# w-dmx-schematic.net
KiCad netlist of a schematic drawn in EasyEDA Pro
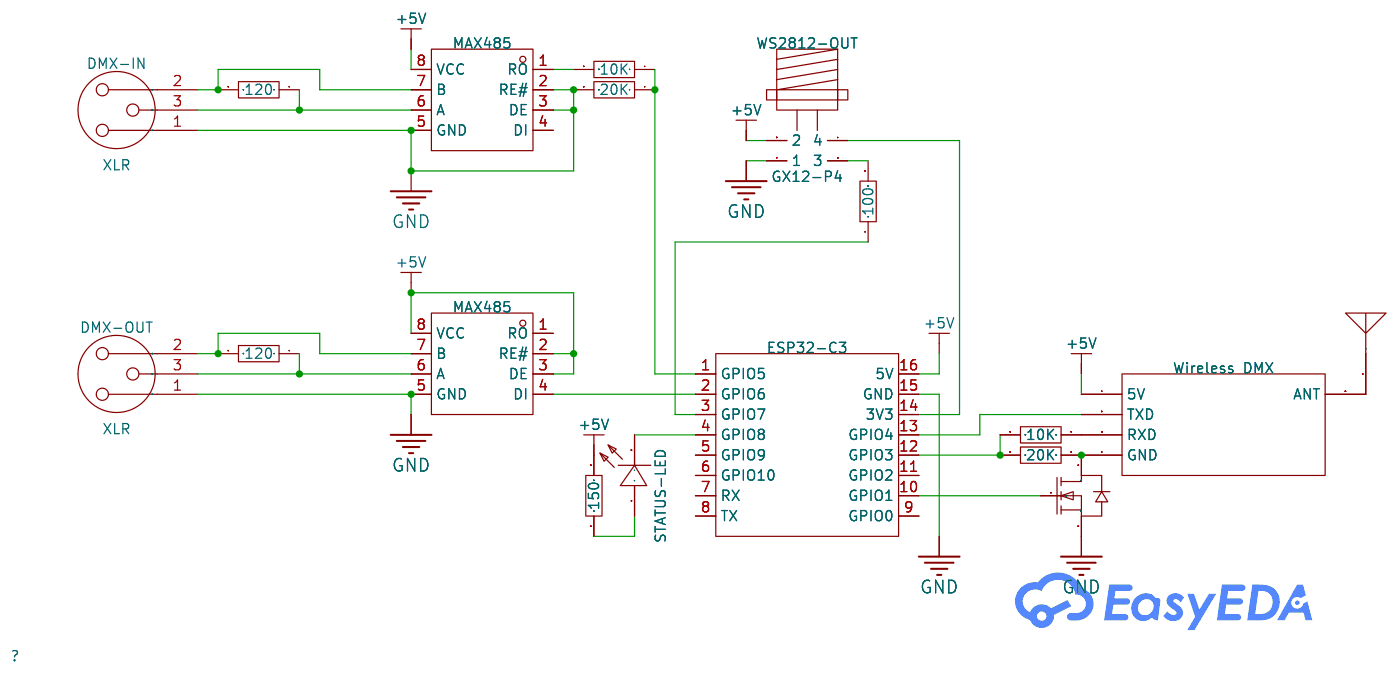
[diagram p0: schematic sheet]

(export (version "E")
  (design (tool "Eeschema 10.0.6"))
  (components
    (comp (ref "DMX-IN")
      (value "XLR")
      (footprint "easyedapro:CONN-TH_XLR-328")
      (description "Number of Pins:3P Gender:Female Mounting Type:Right Angle Current Rating:3A Voltage Rating:50V")
      (fields (field (name "Manufacturer") "HOOYA(皓宇电子)"))
      (libsource (lib "easyedapro") (part "XLR-328"))
    )
    (comp (ref "DMX-OUT")
      (value "XLR")
      (footprint "easyedapro:CONN-TH_XLR-328")
      (description "Number of Pins:3P Gender:Female Mounting Type:Right Angle Current Rating:3A Voltage Rating:50V")
      (fields (field (name "Manufacturer") "HOOYA(皓宇电子)"))
      (libsource (lib "easyedapro") (part "XLR-328"))
    )
    (comp (ref "Q1")
      (value "IRF530")
      (footprint "easyedapro:TO-220AB-3_L10.4-W4.6-P2.54-L")
      (fields (field (name "Manufacturer") "TI(德州仪器)"))
      (libsource (lib "easyedapro") (part "IRF530"))
    )
    (comp (ref "R2") (value "10K") (footprint "easyedapro:R0603") (libsource (lib "easyedapro") (part "Res")))
    (comp (ref "R3") (value "20K") (footprint "easyedapro:R0603") (libsource (lib "easyedapro") (part "Res")))
    (comp (ref "R4") (value "120") (footprint "easyedapro:R0603") (libsource (lib "easyedapro") (part "Res")))
    (comp (ref "R5") (value "120") (footprint "easyedapro:R0603") (libsource (lib "easyedapro") (part "Res")))
    (comp (ref "R6") (value "100") (footprint "easyedapro:R0603") (libsource (lib "easyedapro") (part "Res")))
    (comp (ref "R7") (value "150") (footprint "easyedapro:R0603") (libsource (lib "easyedapro") (part "Res")))
    (comp (ref "R8") (value "10K") (footprint "easyedapro:R0603") (libsource (lib "easyedapro") (part "Res")))
    (comp (ref "R9") (value "20K") (footprint "easyedapro:R0603") (libsource (lib "easyedapro") (part "Res")))
    (comp (ref "STATUS-LED")
      (value "KT-0805Y")
      (footprint "easyedapro:LED0805-R-RD")
      (fields (field (name "Manufacturer") "KENTO"))
      (libsource (lib "easyedapro") (part "17-21SUYC/TR8"))
    )
    (comp (ref "U2")
      (value "MAX485")
      (footprint "easyedapro:SOP-8_L4.9-W3.9-P1.27-LS6.0-BL")
      (fields (field (name "Manufacturer") "ElecSuper(静芯微)"))
      (libsource (lib "easyedapro") (part "MAX485EESA+T(ES)"))
    )
    (comp (ref "U3")
      (value "MAX485")
      (footprint "easyedapro:SOP-8_L4.9-W3.9-P1.27-LS6.0-BL")
      (fields (field (name "Manufacturer") "ElecSuper(静芯微)"))
      (libsource (lib "easyedapro") (part "MAX485EESA+T(ES)"))
    )
    (comp (ref "U4") (value "Wireless DMX") (libsource (lib "easyedapro") (part "Wireless DMX")))
    (comp (ref "U5") (value "~") (libsource (lib "easyedapro") (part "antenna")))
    (comp (ref "U6")
      (value "ESP32-C3")
      (footprint "easyedapro:COMM-SMD_16P-L22.5-W18.0-P2.54-TL")
      (libsource (lib "easyedapro") (part "ESP32C3-SuperMini"))
    )
    (comp (ref "WS2812-OUT")
      (value "GX12-P4")
      (footprint "easyedapro:CONN-TH_GX12C-4P")
      (libsource (lib "easyedapro") (part "WBC0202-150A"))
    )
  )
  (nets
    (net (code "1") (name "+5V") (class "Default")
      (node (ref "R7") (pin "2") (pinfunction "2_2") (pintype "input"))
      (node (ref "U2") (pin "8") (pinfunction "VCC_8") (pintype "unspecified"))
      (node (ref "U3") (pin "2") (pinfunction "RE#_2") (pintype "unspecified"))
      (node (ref "U3") (pin "3") (pinfunction "DE_3") (pintype "unspecified"))
      (node (ref "U3") (pin "8") (pinfunction "VCC_8") (pintype "unspecified"))
      (node (ref "U4") (pin "4") (pinfunction "5V_4") (pintype "input"))
      (node (ref "U6") (pin "16") (pinfunction "5V_16") (pintype "unspecified"))
      (node (ref "WS2812-OUT") (pin "2") (pinfunction "2_2") (pintype "unspecified"))
    )
    (net (code "2") (name "GND") (class "Default")
      (node (ref "DMX-IN") (pin "1") (pinfunction "1_1") (pintype "unspecified"))
      (node (ref "DMX-OUT") (pin "1") (pinfunction "1_1") (pintype "unspecified"))
      (node (ref "Q1") (pin "3") (pinfunction "S_3") (pintype "unspecified"))
      (node (ref "R3") (pin "2") (pinfunction "2_2") (pintype "input"))
      (node (ref "U2") (pin "2") (pinfunction "RE#_2") (pintype "unspecified"))
      (node (ref "U2") (pin "3") (pinfunction "DE_3") (pintype "unspecified"))
      (node (ref "U2") (pin "5") (pinfunction "GND_5") (pintype "unspecified"))
      (node (ref "U3") (pin "5") (pinfunction "GND_5") (pintype "unspecified"))
      (node (ref "U6") (pin "15") (pinfunction "GND_15") (pintype "unspecified"))
      (node (ref "WS2812-OUT") (pin "1") (pinfunction "1_1") (pintype "unspecified"))
    )
    (net (code "3") (name "Net-(Q1-D)") (class "Default")
      (node (ref "Q1") (pin "2") (pinfunction "D_2") (pintype "unspecified"))
      (node (ref "R9") (pin "1") (pinfunction "1_1") (pintype "input"))
      (node (ref "U4") (pin "1") (pinfunction "GND_1") (pintype "input"))
    )
    (net (code "4") (name "Net-(Q1-G)") (class "Default")
      (node (ref "Q1") (pin "1") (pinfunction "G_1") (pintype "unspecified"))
      (node (ref "U6") (pin "10") (pinfunction "GPIO1_10") (pintype "unspecified"))
    )
    (net (code "5") (name "Net-(R6-Pad2)") (class "Default")
      (node (ref "R6") (pin "2") (pinfunction "2_2") (pintype "input"))
      (node (ref "WS2812-OUT") (pin "3") (pinfunction "3_3") (pintype "unspecified"))
    )
    (net (code "6") (name "Net-(STATUS-LED-+)") (class "Default")
      (node (ref "R7") (pin "1") (pinfunction "1_1") (pintype "input"))
      (node (ref "STATUS-LED") (pin "1") (pinfunction "+_1") (pintype "unspecified"))
    )
    (net (code "7") (name "Net-(STATUS-LED--)") (class "Default")
      (node (ref "STATUS-LED") (pin "2") (pinfunction "-_2") (pintype "unspecified"))
      (node (ref "U6") (pin "4") (pinfunction "GPIO8_4") (pintype "unspecified"))
    )
    (net (code "8") (name "Net-(U2-A)") (class "Default")
      (node (ref "DMX-IN") (pin "3") (pinfunction "3_3") (pintype "unspecified"))
      (node (ref "R4") (pin "1") (pinfunction "1_1") (pintype "input"))
      (node (ref "U2") (pin "6") (pinfunction "A_6") (pintype "unspecified"))
    )
    (net (code "9") (name "Net-(U2-B)") (class "Default")
      (node (ref "DMX-IN") (pin "2") (pinfunction "2_2") (pintype "unspecified"))
      (node (ref "R4") (pin "2") (pinfunction "2_2") (pintype "input"))
      (node (ref "U2") (pin "7") (pinfunction "B_7") (pintype "unspecified"))
    )
    (net (code "10") (name "Net-(U2-RO)") (class "Default")
      (node (ref "R2") (pin "2") (pinfunction "2_2") (pintype "input"))
      (node (ref "U2") (pin "1") (pinfunction "RO_1") (pintype "unspecified"))
    )
    (net (code "11") (name "Net-(U3-A)") (class "Default")
      (node (ref "DMX-OUT") (pin "3") (pinfunction "3_3") (pintype "unspecified"))
      (node (ref "R5") (pin "1") (pinfunction "1_1") (pintype "input"))
      (node (ref "U3") (pin "6") (pinfunction "A_6") (pintype "unspecified"))
    )
    (net (code "12") (name "Net-(U3-B)") (class "Default")
      (node (ref "DMX-OUT") (pin "2") (pinfunction "2_2") (pintype "unspecified"))
      (node (ref "R5") (pin "2") (pinfunction "2_2") (pintype "input"))
      (node (ref "U3") (pin "7") (pinfunction "B_7") (pintype "unspecified"))
    )
    (net (code "13") (name "Net-(U3-DI)") (class "Default")
      (node (ref "U3") (pin "4") (pinfunction "DI_4") (pintype "unspecified"))
      (node (ref "U6") (pin "2") (pinfunction "GPIO6_2") (pintype "unspecified"))
    )
    (net (code "14") (name "Net-(U4-ANT)") (class "Default")
      (node (ref "U4") (pin "5") (pinfunction "ANT_5") (pintype "input"))
      (node (ref "U5") (pin "1") (pinfunction "1_1") (pintype "input"))
    )
    (net (code "15") (name "Net-(U4-RXD)") (class "Default")
      (node (ref "R8") (pin "1") (pinfunction "1_1") (pintype "input"))
      (node (ref "U4") (pin "3") (pinfunction "RXD_3") (pintype "input"))
    )
    (net (code "16") (name "Net-(U4-TXD)") (class "Default")
      (node (ref "U4") (pin "2") (pinfunction "TXD_2") (pintype "input"))
      (node (ref "U6") (pin "13") (pinfunction "GPIO4_13") (pintype "unspecified"))
    )
    (net (code "17") (name "Net-(U6-3V3)") (class "Default")
      (node (ref "U6") (pin "14") (pinfunction "3V3_14") (pintype "unspecified"))
      (node (ref "WS2812-OUT") (pin "4") (pinfunction "4_4") (pintype "unspecified"))
    )
    (net (code "18") (name "Net-(U6-GPIO3)") (class "Default")
      (node (ref "R8") (pin "2") (pinfunction "2_2") (pintype "input"))
      (node (ref "R9") (pin "2") (pinfunction "2_2") (pintype "input"))
      (node (ref "U6") (pin "12") (pinfunction "GPIO3_12") (pintype "unspecified"))
    )
    (net (code "19") (name "Net-(U6-GPIO5)") (class "Default")
      (node (ref "R2") (pin "1") (pinfunction "1_1") (pintype "input"))
      (node (ref "R3") (pin "1") (pinfunction "1_1") (pintype "input"))
      (node (ref "U6") (pin "1") (pinfunction "GPIO5_1") (pintype "unspecified"))
    )
    (net (code "20") (name "Net-(U6-GPIO7)") (class "Default")
      (node (ref "R6") (pin "1") (pinfunction "1_1") (pintype "input"))
      (node (ref "U6") (pin "3") (pinfunction "GPIO7_3") (pintype "unspecified"))
    )
    (net (code "21") (name "unconnected-(U2-DI-Pad4)") (class "Default")
      (node (ref "U2") (pin "4") (pinfunction "DI_4") (pintype "unspecified"))
    )
    (net (code "22") (name "unconnected-(U3-RO-Pad1)") (class "Default")
      (node (ref "U3") (pin "1") (pinfunction "RO_1") (pintype "unspecified"))
    )
    (net (code "23") (name "unconnected-(U6-GPIO0-Pad9)") (class "Default")
      (node (ref "U6") (pin "9") (pinfunction "GPIO0_9") (pintype "unspecified"))
    )
    (net (code "24") (name "unconnected-(U6-GPIO2-Pad11)") (class "Default")
      (node (ref "U6") (pin "11") (pinfunction "GPIO2_11") (pintype "unspecified"))
    )
    (net (code "25") (name "unconnected-(U6-GPIO9-Pad5)") (class "Default")
      (node (ref "U6") (pin "5") (pinfunction "GPIO9_5") (pintype "unspecified"))
    )
    (net (code "26") (name "unconnected-(U6-GPIO10-Pad6)") (class "Default")
      (node (ref "U6") (pin "6") (pinfunction "GPIO10_6") (pintype "unspecified"))
    )
    (net (code "27") (name "unconnected-(U6-RX-Pad7)") (class "Default")
      (node (ref "U6") (pin "7") (pinfunction "RX_7") (pintype "unspecified"))
    )
    (net (code "28") (name "unconnected-(U6-TX-Pad8)") (class "Default")
      (node (ref "U6") (pin "8") (pinfunction "TX_8") (pintype "unspecified"))
    )
  )
)
